# Power-up_delay.net
KiCad netlist of a schematic drawn in Altium Designer
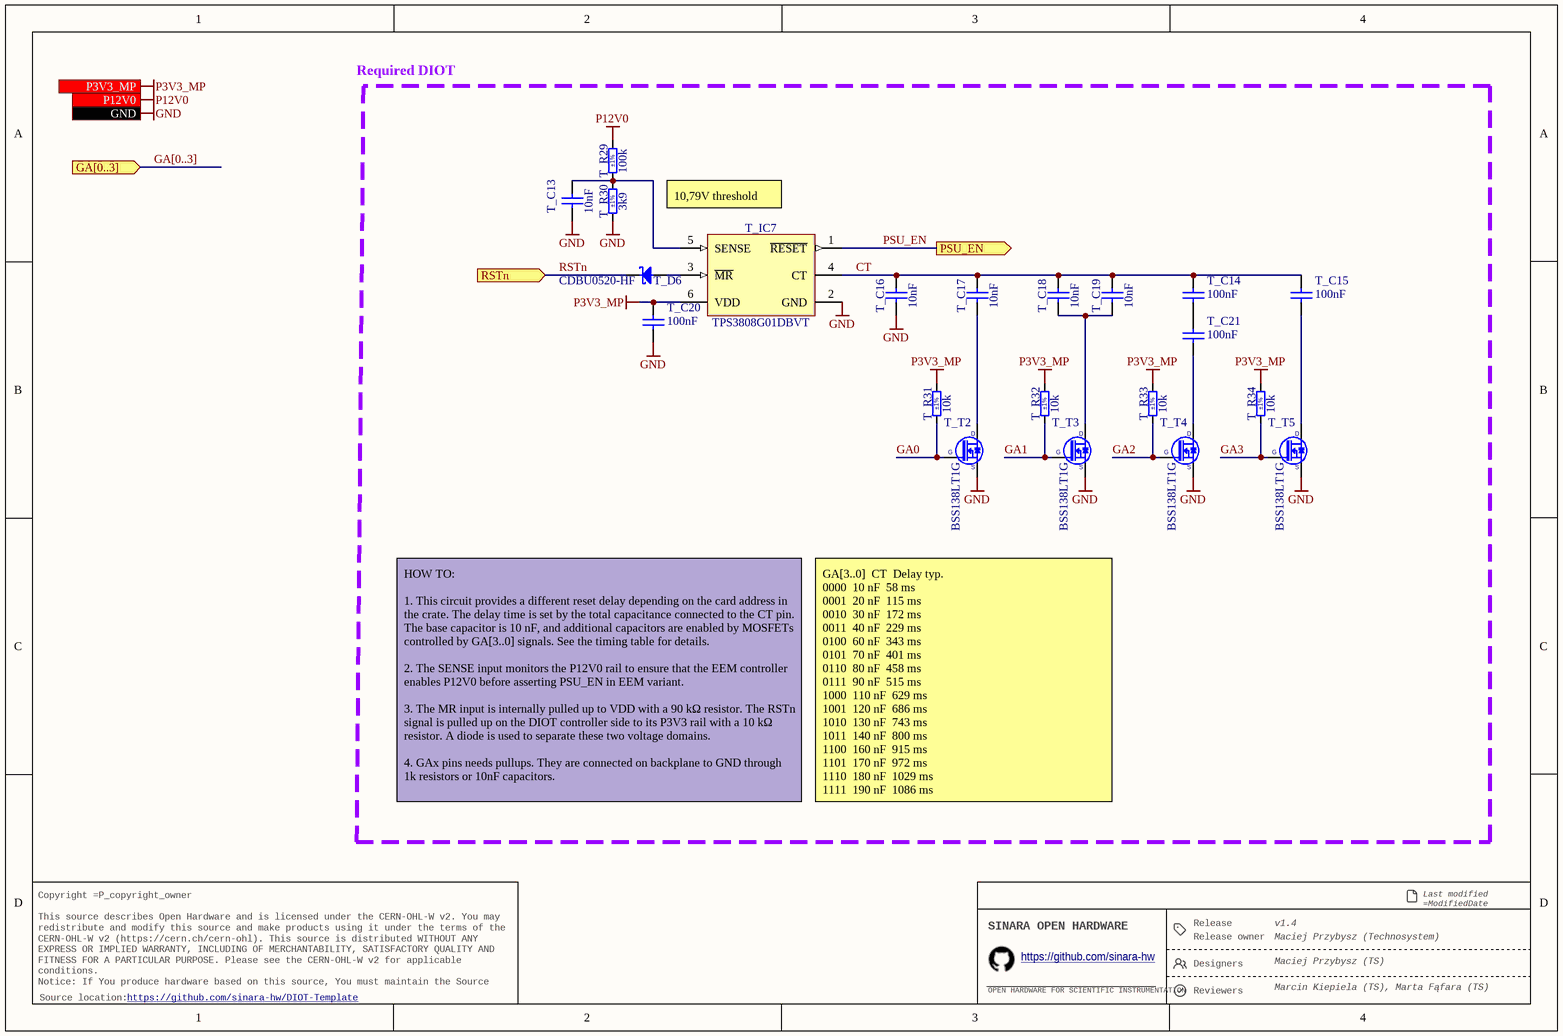
[diagram p0: Power-up_delay.SchDoc]

(export (version "E")
  (design (tool "Eeschema 10.0.6"))
  (components
    (comp (ref "T_C13")
      (value "10nF")
      (footprint "CAPC1005X55N")
      (description "Non-polarised capacitor")
      (fields
        (field (name "PART NUMBER") "CC0402_10NF_50V_5%_X7R")
        (field (name "VOLTAGE") "50V")
        (field (name "AUTHOR") "CERN DEM BC")
      )
      (libsource (lib "Capacitors") (part "Capacitor - non polarized"))
    )
    (comp (ref "T_C14")
      (value "100nF")
      (footprint "CAPC1005X55N")
      (description "Non-polarised capacitor")
      (fields
        (field (name "PART NUMBER") "CC0402_100NF_50V_10%_X7R")
        (field (name "VOLTAGE") "50V")
        (field (name "AUTHOR") "CERN DEM MR")
      )
      (libsource (lib "Capacitors") (part "Capacitor - non polarized"))
    )
    (comp (ref "T_C15")
      (value "100nF")
      (footprint "CAPC1005X55N")
      (description "Non-polarised capacitor")
      (fields
        (field (name "PART NUMBER") "CC0402_100NF_50V_10%_X7R")
        (field (name "VOLTAGE") "50V")
        (field (name "AUTHOR") "CERN DEM MR")
      )
      (libsource (lib "Capacitors") (part "Capacitor - non polarized"))
    )
    (comp (ref "T_C16")
      (value "10nF")
      (footprint "CAPC1005X55N")
      (description "Non-polarised capacitor")
      (fields
        (field (name "PART NUMBER") "CC0402_10NF_50V_5%_X7R")
        (field (name "VOLTAGE") "50V")
        (field (name "AUTHOR") "CERN DEM BC")
      )
      (libsource (lib "Capacitors") (part "Capacitor - non polarized"))
    )
    (comp (ref "T_C17")
      (value "10nF")
      (footprint "CAPC1005X55N")
      (description "Non-polarised capacitor")
      (fields
        (field (name "PART NUMBER") "CC0402_10NF_50V_5%_X7R")
        (field (name "VOLTAGE") "50V")
        (field (name "AUTHOR") "CERN DEM BC")
      )
      (libsource (lib "Capacitors") (part "Capacitor - non polarized"))
    )
    (comp (ref "T_C18")
      (value "10nF")
      (footprint "CAPC1005X55N")
      (description "Non-polarised capacitor")
      (fields
        (field (name "PART NUMBER") "CC0402_10NF_50V_5%_X7R")
        (field (name "VOLTAGE") "50V")
        (field (name "AUTHOR") "CERN DEM BC")
      )
      (libsource (lib "Capacitors") (part "Capacitor - non polarized"))
    )
    (comp (ref "T_C19")
      (value "10nF")
      (footprint "CAPC1005X55N")
      (description "Non-polarised capacitor")
      (fields
        (field (name "PART NUMBER") "CC0402_10NF_50V_5%_X7R")
        (field (name "VOLTAGE") "50V")
        (field (name "AUTHOR") "CERN DEM BC")
      )
      (libsource (lib "Capacitors") (part "Capacitor - non polarized"))
    )
    (comp (ref "T_C20")
      (value "100nF")
      (footprint "CAPC1005X55N")
      (description "Non-polarised capacitor")
      (fields
        (field (name "PART NUMBER") "CC0402_100NF_50V_10%_X7R")
        (field (name "VOLTAGE") "50V")
        (field (name "AUTHOR") "CERN DEM MR")
      )
      (libsource (lib "Capacitors") (part "Capacitor - non polarized"))
    )
    (comp (ref "T_C21")
      (value "100nF")
      (footprint "CAPC1005X55N")
      (description "Non-polarised capacitor")
      (fields
        (field (name "PART NUMBER") "CC0402_100NF_50V_10%_X7R")
        (field (name "VOLTAGE") "50V")
        (field (name "AUTHOR") "CERN DEM MR")
      )
      (libsource (lib "Capacitors") (part "Capacitor - non polarized"))
    )
    (comp (ref "T_D6")
      (value "CDBU0520-HF")
      (footprint "SOD-523F")
      (description "Schottky Diode")
      (fields
        (field (name "VOLTAGE") "20V")
        (field (name "POWER") "500mA")
        (field (name "AUTHOR") "CERN DEM HF")
      )
      (libsource (lib "ICs And Semiconductors") (part "Diode Schottky"))
    )
    (comp (ref "T_IC7")
      (value "TPS3808G01DBVT")
      (footprint "SOT95P280X145-6N")
      (description "Low Quiescent Current, Programmable-Delay Supervisory Circuit")
      (fields
        (field (name "MANUFACTURER") "TEXAS INSTRUMENTS")
        (field (name "MANUFACTURER PART NUMBER") "TPS3808G01DBV")
        (field (name "AUTHOR") "CERN DEM JLC")
      )
      (libsource (lib "ICs And Semiconductors") (part "TPS3808xxxDBV"))
    )
    (comp (ref "T_R29")
      (value "100k")
      (footprint "RESC1005X40N")
      (description "Resistor - 1%")
      (fields
        (field (name "TOLERANCE") "±1%")
        (field (name "PART NUMBER") "R0402_100K_1%_0.0625W_100PPM")
        (field (name "POWER") "0.0625W")
        (field (name "AUTHOR") "CERN DEM JLC")
      )
      (libsource (lib "Resistors") (part "Resistor - 1%"))
    )
    (comp (ref "T_R30")
      (value "3k9")
      (footprint "RESC1005X40N")
      (description "Resistor - 1%")
      (fields
        (field (name "TOLERANCE") "±1%")
        (field (name "PART NUMBER") "R0402_3K9_1%_0.0625W_100PPM")
        (field (name "POWER") "0.0625W")
        (field (name "AUTHOR") "CERN DEM JLC")
      )
      (libsource (lib "Resistors") (part "Resistor - 1%"))
    )
    (comp (ref "T_R31")
      (value "10k")
      (footprint "RESC1005X40N")
      (description "Resistor - 1%")
      (fields
        (field (name "TOLERANCE") "±1%")
        (field (name "PART NUMBER") "R0402_10K_1%_0.0625W_100PPM")
        (field (name "POWER") "0.0625W")
        (field (name "AUTHOR") "CERN DEM JLC")
      )
      (libsource (lib "Resistors") (part "Resistor - 1%"))
    )
    (comp (ref "T_R32")
      (value "10k")
      (footprint "RESC1005X40N")
      (description "Resistor - 1%")
      (fields
        (field (name "TOLERANCE") "±1%")
        (field (name "PART NUMBER") "R0402_10K_1%_0.0625W_100PPM")
        (field (name "POWER") "0.0625W")
        (field (name "AUTHOR") "CERN DEM JLC")
      )
      (libsource (lib "Resistors") (part "Resistor - 1%"))
    )
    (comp (ref "T_R33")
      (value "10k")
      (footprint "RESC1005X40N")
      (description "Resistor - 1%")
      (fields
        (field (name "TOLERANCE") "±1%")
        (field (name "PART NUMBER") "R0402_10K_1%_0.0625W_100PPM")
        (field (name "POWER") "0.0625W")
        (field (name "AUTHOR") "CERN DEM JLC")
      )
      (libsource (lib "Resistors") (part "Resistor - 1%"))
    )
    (comp (ref "T_R34")
      (value "10k")
      (footprint "RESC1005X40N")
      (description "Resistor - 1%")
      (fields
        (field (name "TOLERANCE") "±1%")
        (field (name "PART NUMBER") "R0402_10K_1%_0.0625W_100PPM")
        (field (name "POWER") "0.0625W")
        (field (name "AUTHOR") "CERN DEM JLC")
      )
      (libsource (lib "Resistors") (part "Resistor - 1%"))
    )
    (comp (ref "T_T2")
      (value "BSS138LT1G")
      (footprint "SOT95P240X110-3N")
      (description "N-CHANNEL MOSFET WITH DIODE")
      (fields
        (field (name "MANUFACTURER") "ON SEMICONDUCTOR")
        (field (name "MANUFACTURER PART NUMBER") "BSS138L")
        (field (name "AUTHOR") "CERN DEM JLC")
      )
      (libsource (lib "ICs And Semiconductors") (part "N-MOSFET-D 1G 2S 3D"))
    )
    (comp (ref "T_T3")
      (value "BSS138LT1G")
      (footprint "SOT95P240X110-3N")
      (description "N-CHANNEL MOSFET WITH DIODE")
      (fields
        (field (name "MANUFACTURER") "ON SEMICONDUCTOR")
        (field (name "MANUFACTURER PART NUMBER") "BSS138L")
        (field (name "AUTHOR") "CERN DEM JLC")
      )
      (libsource (lib "ICs And Semiconductors") (part "N-MOSFET-D 1G 2S 3D"))
    )
    (comp (ref "T_T4")
      (value "BSS138LT1G")
      (footprint "SOT95P240X110-3N")
      (description "N-CHANNEL MOSFET WITH DIODE")
      (fields
        (field (name "MANUFACTURER") "ON SEMICONDUCTOR")
        (field (name "MANUFACTURER PART NUMBER") "BSS138L")
        (field (name "AUTHOR") "CERN DEM JLC")
      )
      (libsource (lib "ICs And Semiconductors") (part "N-MOSFET-D 1G 2S 3D"))
    )
    (comp (ref "T_T5")
      (value "BSS138LT1G")
      (footprint "SOT95P240X110-3N")
      (description "N-CHANNEL MOSFET WITH DIODE")
      (fields
        (field (name "MANUFACTURER") "ON SEMICONDUCTOR")
        (field (name "MANUFACTURER PART NUMBER") "BSS138L")
        (field (name "AUTHOR") "CERN DEM JLC")
      )
      (libsource (lib "ICs And Semiconductors") (part "N-MOSFET-D 1G 2S 3D"))
    )
  )
  (nets
    (net (code "1") (name "/CT") (class "Default")
      (node (ref "T_C14") (pin "2") (pinfunction "2_2") (pintype "passive"))
      (node (ref "T_C15") (pin "2") (pinfunction "2_2") (pintype "passive"))
      (node (ref "T_C16") (pin "2") (pinfunction "2_2") (pintype "passive"))
      (node (ref "T_C17") (pin "2") (pinfunction "2_2") (pintype "passive"))
      (node (ref "T_C18") (pin "2") (pinfunction "2_2") (pintype "passive"))
      (node (ref "T_C19") (pin "2") (pinfunction "2_2") (pintype "passive"))
      (node (ref "T_IC7") (pin "4") (pinfunction "CT_4") (pintype "passive"))
    )
    (net (code "2") (name "/GA0") (class "Default")
      (node (ref "T_R31") (pin "1") (pinfunction "1_1") (pintype "passive"))
      (node (ref "T_T2") (pin "1") (pinfunction "G_1") (pintype "passive"))
    )
    (net (code "3") (name "/GA1") (class "Default")
      (node (ref "T_R32") (pin "1") (pinfunction "1_1") (pintype "passive"))
      (node (ref "T_T3") (pin "1") (pinfunction "G_1") (pintype "passive"))
    )
    (net (code "4") (name "/GA2") (class "Default")
      (node (ref "T_R33") (pin "1") (pinfunction "1_1") (pintype "passive"))
      (node (ref "T_T4") (pin "1") (pinfunction "G_1") (pintype "passive"))
    )
    (net (code "5") (name "/GA3") (class "Default")
      (node (ref "T_R34") (pin "1") (pinfunction "1_1") (pintype "passive"))
      (node (ref "T_T5") (pin "1") (pinfunction "G_1") (pintype "passive"))
    )
    (net (code "7") (name "/PSU_EN") (class "Default")
      (node (ref "T_IC7") (pin "1") (pinfunction "~{RESET}_1") (pintype "output"))
    )
    (net (code "8") (name "/RSTn") (class "Default")
      (node (ref "T_D6") (pin "1") (pinfunction "C_1") (pintype "passive"))
    )
    (net (code "9") (name "GND") (class "Default")
      (node (ref "T_C13") (pin "2") (pinfunction "2_2") (pintype "passive"))
      (node (ref "T_C16") (pin "1") (pinfunction "1_1") (pintype "passive"))
      (node (ref "T_C20") (pin "1") (pinfunction "1_1") (pintype "passive"))
      (node (ref "T_IC7") (pin "2") (pinfunction "GND_2") (pintype "power_in"))
      (node (ref "T_R30") (pin "1") (pinfunction "1_1") (pintype "passive"))
      (node (ref "T_T2") (pin "2") (pinfunction "S_2") (pintype "passive"))
      (node (ref "T_T3") (pin "2") (pinfunction "S_2") (pintype "passive"))
      (node (ref "T_T4") (pin "2") (pinfunction "S_2") (pintype "passive"))
      (node (ref "T_T5") (pin "2") (pinfunction "S_2") (pintype "passive"))
    )
    (net (code "10") (name "Net-(T_C14-Pad1)") (class "Default")
      (node (ref "T_C14") (pin "1") (pinfunction "1_1") (pintype "passive"))
      (node (ref "T_C21") (pin "2") (pinfunction "2_2") (pintype "passive"))
    )
    (net (code "11") (name "Net-(T_D6-A)") (class "Default")
      (node (ref "T_D6") (pin "2") (pinfunction "A_2") (pintype "passive"))
      (node (ref "T_IC7") (pin "3") (pinfunction "~{MR}_3") (pintype "input"))
    )
    (net (code "12") (name "Net-(T_IC7-SENSE)") (class "Default")
      (node (ref "T_C13") (pin "1") (pinfunction "1_1") (pintype "passive"))
      (node (ref "T_IC7") (pin "5") (pinfunction "SENSE_5") (pintype "input"))
      (node (ref "T_R29") (pin "2") (pinfunction "2_2") (pintype "passive"))
      (node (ref "T_R30") (pin "2") (pinfunction "2_2") (pintype "passive"))
    )
    (net (code "13") (name "Net-(T_T2-D)") (class "Default")
      (node (ref "T_C17") (pin "1") (pinfunction "1_1") (pintype "passive"))
      (node (ref "T_T2") (pin "3") (pinfunction "D_3") (pintype "passive"))
    )
    (net (code "14") (name "Net-(T_T3-D)") (class "Default")
      (node (ref "T_C18") (pin "1") (pinfunction "1_1") (pintype "passive"))
      (node (ref "T_C19") (pin "1") (pinfunction "1_1") (pintype "passive"))
      (node (ref "T_T3") (pin "3") (pinfunction "D_3") (pintype "passive"))
    )
    (net (code "15") (name "Net-(T_T4-D)") (class "Default")
      (node (ref "T_C21") (pin "1") (pinfunction "1_1") (pintype "passive"))
      (node (ref "T_T4") (pin "3") (pinfunction "D_3") (pintype "passive"))
    )
    (net (code "16") (name "Net-(T_T5-D)") (class "Default")
      (node (ref "T_C15") (pin "1") (pinfunction "1_1") (pintype "passive"))
      (node (ref "T_T5") (pin "3") (pinfunction "D_3") (pintype "passive"))
    )
    (net (code "17") (name "P3V3_MP") (class "Default")
      (node (ref "T_C20") (pin "2") (pinfunction "2_2") (pintype "passive"))
      (node (ref "T_IC7") (pin "6") (pinfunction "VDD_6") (pintype "power_in"))
      (node (ref "T_R31") (pin "2") (pinfunction "2_2") (pintype "passive"))
      (node (ref "T_R32") (pin "2") (pinfunction "2_2") (pintype "passive"))
      (node (ref "T_R33") (pin "2") (pinfunction "2_2") (pintype "passive"))
      (node (ref "T_R34") (pin "2") (pinfunction "2_2") (pintype "passive"))
    )
    (net (code "18") (name "P12V0") (class "Default")
      (node (ref "T_R29") (pin "1") (pinfunction "1_1") (pintype "passive"))
    )
  )
)
